# Pixel-2.net
KiCad netlist of a schematic drawn in EAGLE
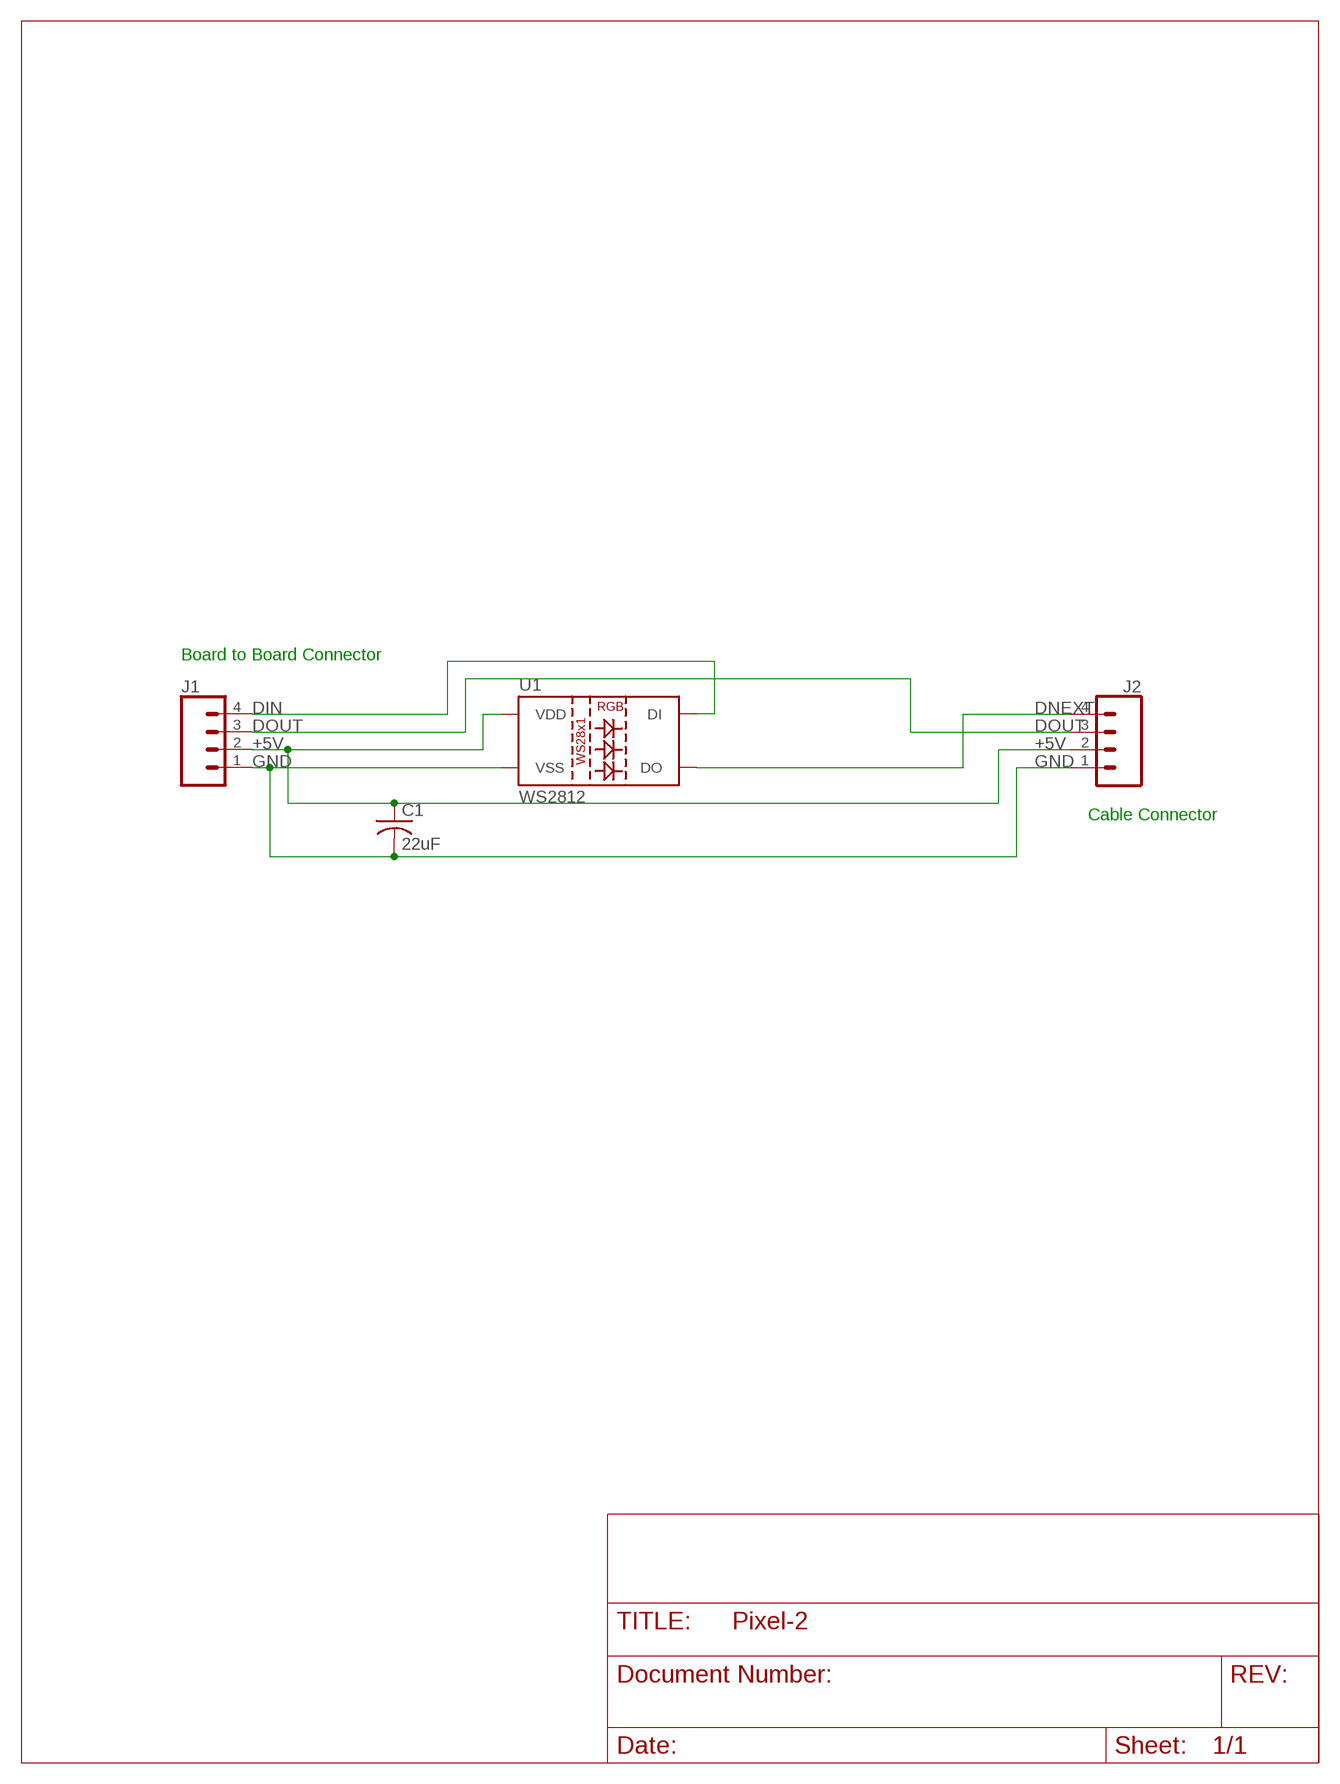
[diagram p0: schematic, sheet 1]

(export (version "E")
  (design (tool "Eeschema 10.0.6"))
  (components
    (comp (ref "C1")
      (value "22uF")
      (footprint "eagle-import:C0402")
      (libsource (lib "eagle-import") (part "C-USC0402"))
    )
    (comp (ref "J1")
      (value "CONN_04")
      (footprint "eagle-import:1X04")
      (libsource (lib "eagle-import") (part "CONN_04"))
    )
    (comp (ref "J2")
      (value "CONN_04")
      (footprint "eagle-import:1X04")
      (libsource (lib "eagle-import") (part "CONN_04"))
    )
    (comp (ref "U1")
      (value "WS2812")
      (footprint "eagle-import:LED-TRICOLOR-5050-IC")
      (libsource (lib "eagle-import") (part "WS2812{dblquote}"))
    )
  )
  (nets
    (net (code "1") (name "/+5V") (class "Default")
      (node (ref "C1") (pin "1") (pinfunction "1_1") (pintype "passive"))
      (node (ref "J1") (pin "2") (pinfunction "2_2") (pintype "passive"))
      (node (ref "J2") (pin "2") (pinfunction "2_2") (pintype "passive"))
      (node (ref "U1") (pin "3") (pinfunction "VDD_3") (pintype "bidirectional"))
      (node (ref "U1") (pin "5") (pinfunction "VDD_5") (pintype "bidirectional"))
    )
    (net (code "2") (name "/DIN") (class "Default")
      (node (ref "J1") (pin "4") (pinfunction "4_4") (pintype "passive"))
      (node (ref "U1") (pin "2") (pinfunction "DI_2") (pintype "bidirectional"))
    )
    (net (code "3") (name "/DNEXT") (class "Default")
      (node (ref "J2") (pin "4") (pinfunction "4_4") (pintype "passive"))
      (node (ref "U1") (pin "1") (pinfunction "DO_1") (pintype "bidirectional"))
    )
    (net (code "4") (name "/DOUT") (class "Default")
      (node (ref "J1") (pin "3") (pinfunction "3_3") (pintype "passive"))
      (node (ref "J2") (pin "3") (pinfunction "3_3") (pintype "passive"))
    )
    (net (code "5") (name "/GND") (class "Default")
      (node (ref "C1") (pin "2") (pinfunction "2_2") (pintype "passive"))
      (node (ref "J1") (pin "1") (pinfunction "1_1") (pintype "passive"))
      (node (ref "J2") (pin "1") (pinfunction "1_1") (pintype "passive"))
      (node (ref "U1") (pin "6") (pinfunction "VSS_6") (pintype "bidirectional"))
    )
  )
)
